# isolated_module_v4.net
KiCad netlist of a schematic drawn in EAGLE
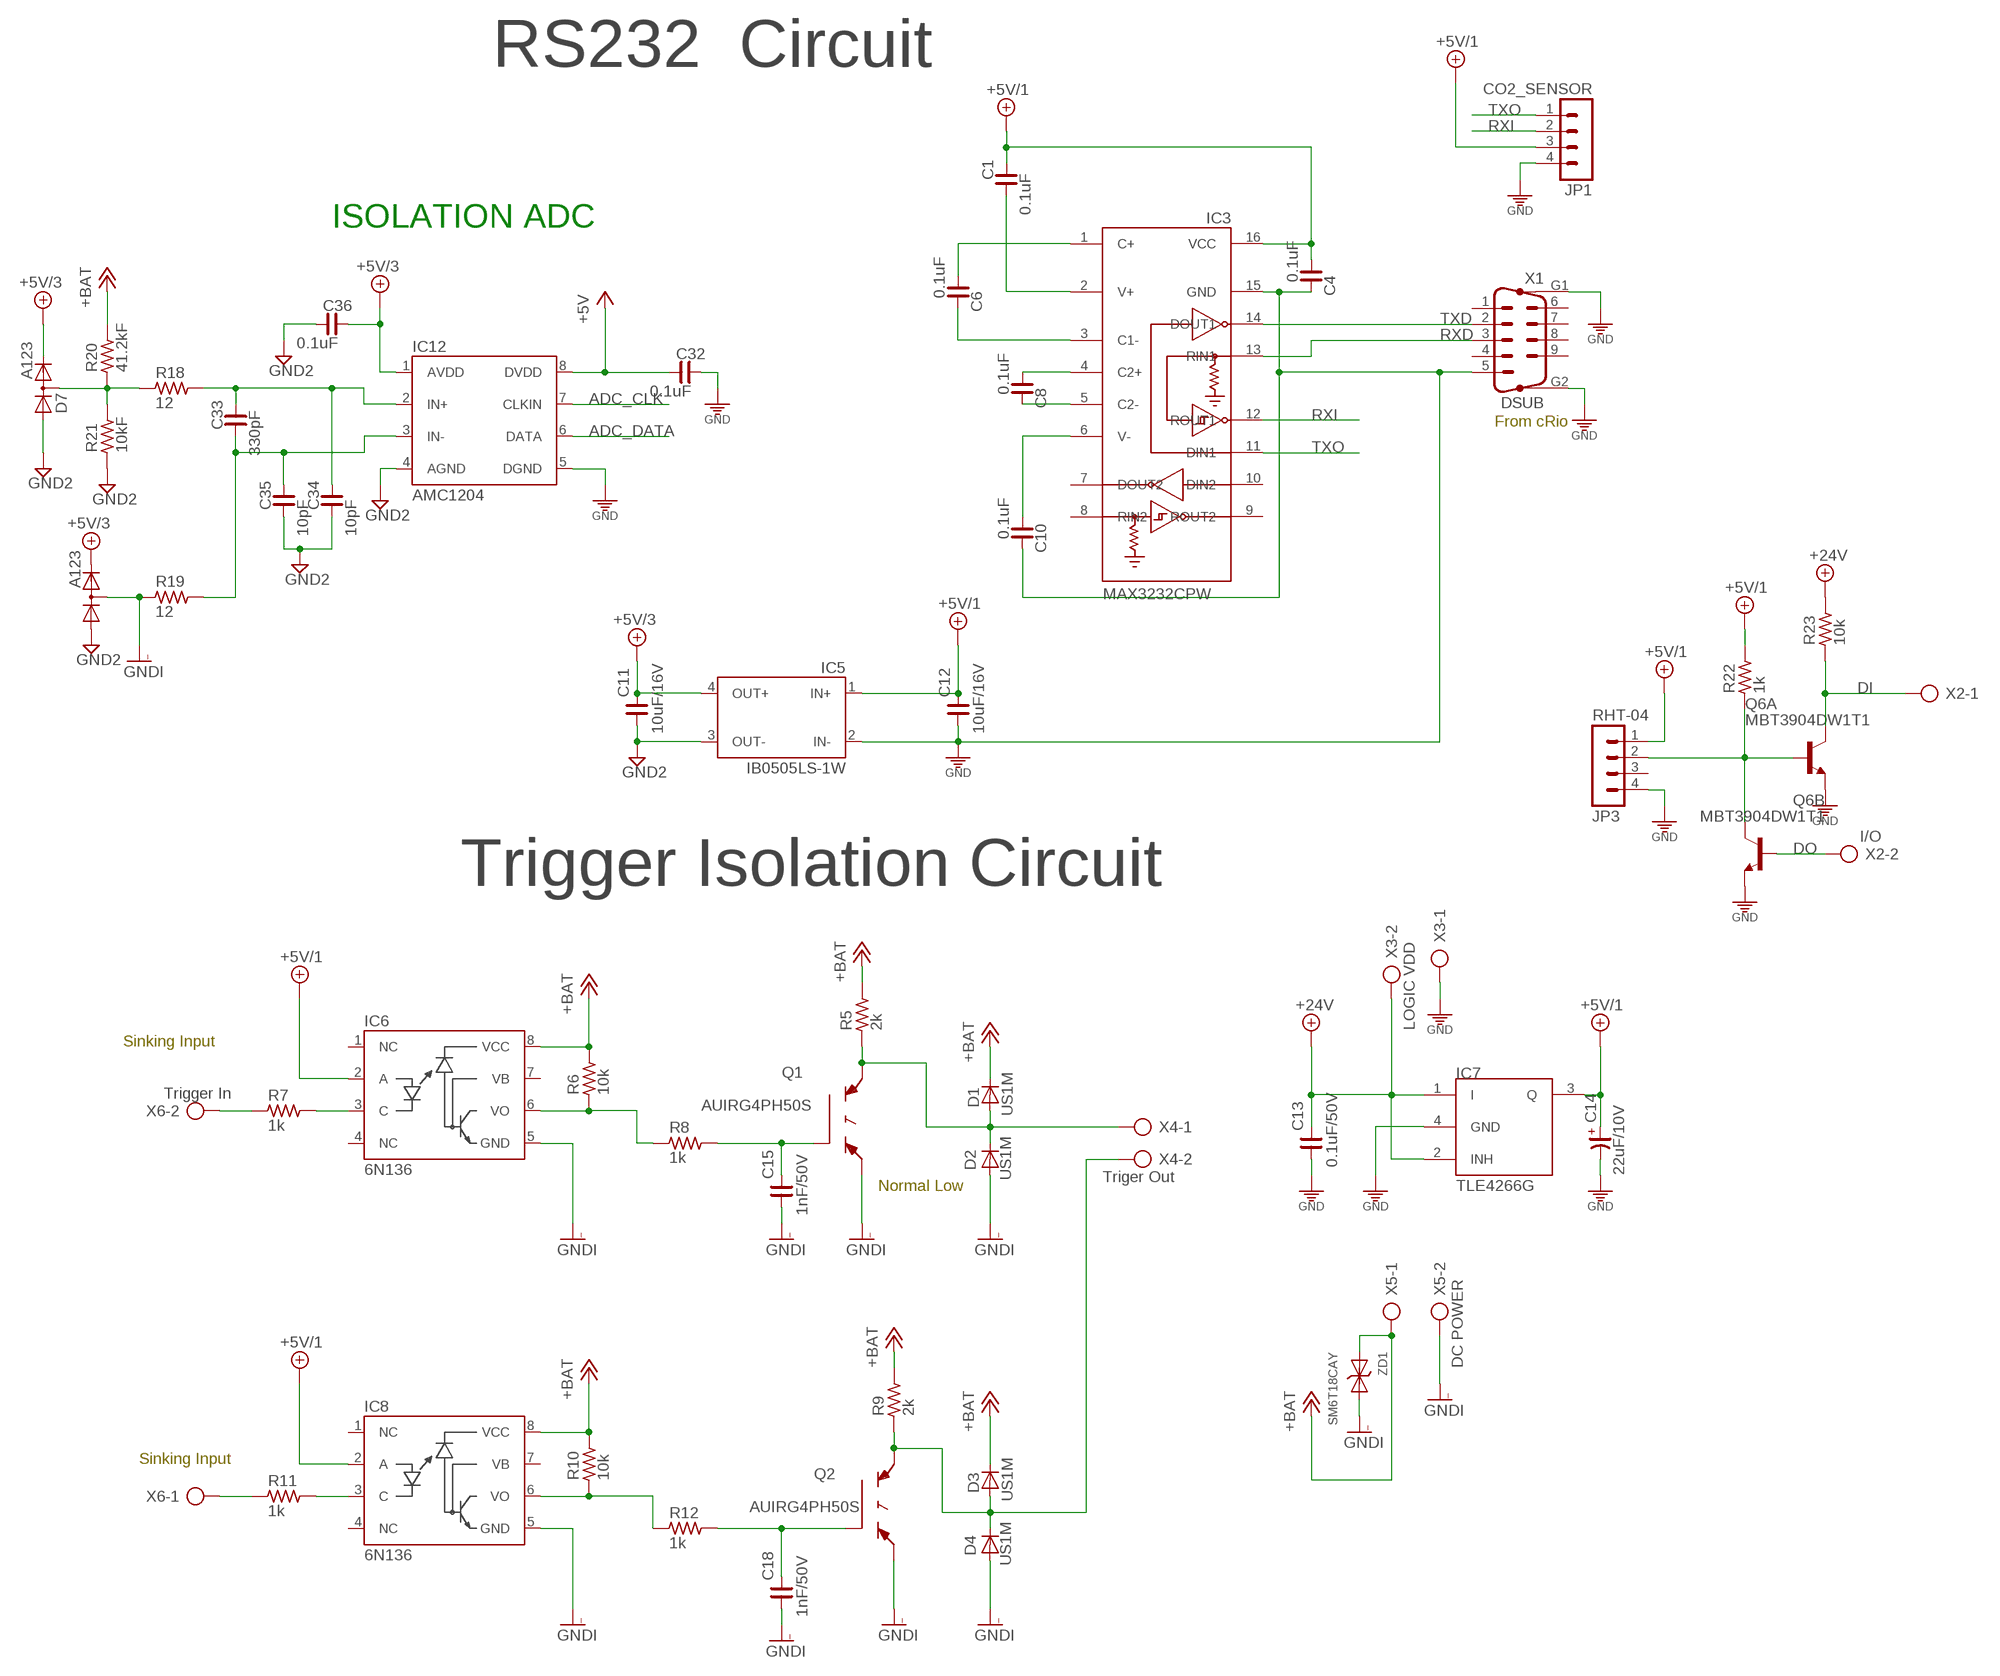
[diagram p0: schematic, sheet 1]

(export (version "E")
  (design (tool "Eeschema 10.0.6"))
  (components
    (comp (ref "C1")
      (value "0.1uF")
      (footprint "eagle-import:C0603")
      (libsource (lib "eagle-import") (part "cona_lib_C_0603"))
    )
    (comp (ref "C4")
      (value "0.1uF")
      (footprint "eagle-import:C0603")
      (libsource (lib "eagle-import") (part "cona_lib_C_0603"))
    )
    (comp (ref "C6")
      (value "0.1uF")
      (footprint "eagle-import:C0603")
      (libsource (lib "eagle-import") (part "cona_lib_C_0603"))
    )
    (comp (ref "C8")
      (value "0.1uF")
      (footprint "eagle-import:C0603")
      (libsource (lib "eagle-import") (part "cona_lib_C_0603"))
    )
    (comp (ref "C10")
      (value "0.1uF")
      (footprint "eagle-import:C0603")
      (libsource (lib "eagle-import") (part "cona_lib_C_0603"))
    )
    (comp (ref "C11")
      (value "10uF/16V")
      (footprint "eagle-import:C1210")
      (libsource (lib "eagle-import") (part "rc-master-smd_C_1210"))
    )
    (comp (ref "C12")
      (value "10uF/16V")
      (footprint "eagle-import:C1210")
      (libsource (lib "eagle-import") (part "rc-master-smd_C_1210"))
    )
    (comp (ref "C13")
      (value "0.1uF/50V")
      (footprint "eagle-import:C1608-")
      (libsource (lib "eagle-import") (part "C_0603"))
    )
    (comp (ref "C14")
      (value "22uF/10V")
      (footprint "eagle-import:T3258")
      (libsource (lib "eagle-import") (part "TANTAL3528"))
    )
    (comp (ref "C15")
      (value "1nF/50V")
      (footprint "eagle-import:C1608-")
      (libsource (lib "eagle-import") (part "C_0603"))
    )
    (comp (ref "C18")
      (value "1nF/50V")
      (footprint "eagle-import:C1608-")
      (libsource (lib "eagle-import") (part "C_0603"))
    )
    (comp (ref "C32")
      (value "0.1uF")
      (footprint "eagle-import:C0603")
      (libsource (lib "eagle-import") (part "cona_lib_C_0603"))
    )
    (comp (ref "C33")
      (value "330pF")
      (footprint "eagle-import:C0603")
      (libsource (lib "eagle-import") (part "cona_lib_C_0603"))
    )
    (comp (ref "C34")
      (value "10pF")
      (footprint "eagle-import:C0603")
      (libsource (lib "eagle-import") (part "cona_lib_C_0603"))
    )
    (comp (ref "C35")
      (value "10pF")
      (footprint "eagle-import:C0603")
      (libsource (lib "eagle-import") (part "cona_lib_C_0603"))
    )
    (comp (ref "C36")
      (value "0.1uF")
      (footprint "eagle-import:C0603")
      (libsource (lib "eagle-import") (part "cona_lib_C_0603"))
    )
    (comp (ref "D1")
      (value "US1M")
      (footprint "eagle-import:DO-214AC")
      (libsource (lib "eagle-import") (part "DIODE-DO-214AC"))
    )
    (comp (ref "D2")
      (value "US1M")
      (footprint "eagle-import:DO-214AC")
      (libsource (lib "eagle-import") (part "DIODE-DO-214AC"))
    )
    (comp (ref "D3")
      (value "US1M")
      (footprint "eagle-import:DO-214AC")
      (libsource (lib "eagle-import") (part "DIODE-DO-214AC"))
    )
    (comp (ref "D4")
      (value "US1M")
      (footprint "eagle-import:DO-214AC")
      (libsource (lib "eagle-import") (part "DIODE-DO-214AC"))
    )
    (comp (ref "D7")
      (value "A123")
      (footprint "eagle-import:SOT23")
      (libsource (lib "eagle-import") (part "DIODE_2CACA-SOT23"))
    )
    (comp (ref "D8")
      (value "A123")
      (footprint "eagle-import:SOT23")
      (libsource (lib "eagle-import") (part "DIODE_2CACA-SOT23"))
    )
    (comp (ref "IC3")
      (value "MAX3232CPW")
      (footprint "eagle-import:PW_R-PDSO-G16")
      (libsource (lib "eagle-import") (part "MAX3232MAX232CPW"))
    )
    (comp (ref "IC5")
      (value "IB0505LS-1W")
      (footprint "eagle-import:DSP1N5S5")
      (libsource (lib "eagle-import") (part "DSP1N5S5"))
    )
    (comp (ref "IC6")
      (value "6N136")
      (footprint "eagle-import:DIL08")
      (libsource (lib "eagle-import") (part "6N136"))
    )
    (comp (ref "IC7")
      (value "TLE4266G")
      (footprint "eagle-import:SOT223-4")
      (libsource (lib "eagle-import") (part "TLE4266G"))
    )
    (comp (ref "IC8")
      (value "6N136")
      (footprint "eagle-import:DIL08")
      (libsource (lib "eagle-import") (part "6N136"))
    )
    (comp (ref "IC12")
      (value "AMC1204")
      (footprint "eagle-import:SO08")
      (libsource (lib "eagle-import") (part "AMC1204"))
    )
    (comp (ref "JP1")
      (value "CO2_SENSOR")
      (footprint "eagle-import:MA04-1-S")
      (libsource (lib "eagle-import") (part "MA04-1SMALL"))
    )
    (comp (ref "JP3")
      (value "RHT-04")
      (footprint "eagle-import:MA04-MOL_N")
      (libsource (lib "eagle-import") (part "MA04-1MOL-N"))
    )
    (comp (ref "Q1")
      (value "AUIRG4PH50S")
      (footprint "eagle-import:TO247AC")
      (libsource (lib "eagle-import") (part "IGBTAC"))
    )
    (comp (ref "Q2")
      (value "AUIRG4PH50S")
      (footprint "eagle-import:TO247AC")
      (libsource (lib "eagle-import") (part "IGBTAC"))
    )
    (comp (ref "Q6")
      (value "MBT3904DW1T1")
      (footprint "eagle-import:UMT6")
      (fields (field (name "MPN") "UMX1NTN"))
      (libsource (lib "eagle-import") (part "UMX1N"))
    )
    (comp (ref "R5")
      (value "2k")
      (footprint "eagle-import:R0805")
      (libsource (lib "eagle-import") (part "R_0805"))
    )
    (comp (ref "R6")
      (value "10k")
      (footprint "eagle-import:R0603")
      (libsource (lib "eagle-import") (part "R_0603"))
    )
    (comp (ref "R7")
      (value "1k")
      (footprint "eagle-import:R0603")
      (libsource (lib "eagle-import") (part "R_0603"))
    )
    (comp (ref "R8")
      (value "1k")
      (footprint "eagle-import:R0603")
      (libsource (lib "eagle-import") (part "R_0603"))
    )
    (comp (ref "R9")
      (value "2k")
      (footprint "eagle-import:R0805")
      (libsource (lib "eagle-import") (part "R_0805"))
    )
    (comp (ref "R10")
      (value "10k")
      (footprint "eagle-import:R0603")
      (libsource (lib "eagle-import") (part "R_0603"))
    )
    (comp (ref "R11")
      (value "1k")
      (footprint "eagle-import:R0603")
      (libsource (lib "eagle-import") (part "R_0603"))
    )
    (comp (ref "R12")
      (value "1k")
      (footprint "eagle-import:R0603")
      (libsource (lib "eagle-import") (part "R_0603"))
    )
    (comp (ref "R18")
      (value "12")
      (footprint "eagle-import:R0603")
      (libsource (lib "eagle-import") (part "R_0603"))
    )
    (comp (ref "R19")
      (value "12")
      (footprint "eagle-import:R0603")
      (libsource (lib "eagle-import") (part "R_0603"))
    )
    (comp (ref "R20")
      (value "41.2kF")
      (footprint "eagle-import:R0603")
      (libsource (lib "eagle-import") (part "R_0603"))
    )
    (comp (ref "R21")
      (value "10kF")
      (footprint "eagle-import:R0603")
      (libsource (lib "eagle-import") (part "R_0603"))
    )
    (comp (ref "R22")
      (value "1k")
      (footprint "eagle-import:R0603")
      (libsource (lib "eagle-import") (part "R_0603"))
    )
    (comp (ref "R23")
      (value "10k")
      (footprint "eagle-import:R0603")
      (libsource (lib "eagle-import") (part "R_0603"))
    )
    (comp (ref "X1")
      (value "DSUB")
      (footprint "eagle-import:M09HP")
      (fields (field (name "OC_FARNELL") "unknown") (field (name "OC_NEWARK") "unknown"))
      (libsource (lib "eagle-import") (part "M09HP"))
    )
    (comp (ref "X2")
      (value "I/O")
      (footprint "eagle-import:AK300_2")
      (libsource (lib "eagle-import") (part "AK300/2"))
    )
    (comp (ref "X3")
      (value "LOGIC VDD")
      (footprint "eagle-import:AK300_2")
      (libsource (lib "eagle-import") (part "AK300/2"))
    )
    (comp (ref "X4")
      (value "Triger Out")
      (footprint "eagle-import:AK300_2")
      (libsource (lib "eagle-import") (part "AK300/2"))
    )
    (comp (ref "X5")
      (value "DC POWER")
      (footprint "eagle-import:AK300_2")
      (libsource (lib "eagle-import") (part "AK300/2"))
    )
    (comp (ref "X6")
      (value "Trigger In")
      (footprint "eagle-import:AK300_2")
      (libsource (lib "eagle-import") (part "AK300/2"))
    )
    (comp (ref "ZD1")
      (value "SM6T18CAY")
      (footprint "eagle-import:SMB")
      (libsource (lib "eagle-import") (part "ZDSM6T33CAY"))
    )
  )
  (nets
    (net (code "1") (name "+5V") (class "Default")
      (node (ref "C32") (pin "2") (pinfunction "2_2") (pintype "passive"))
      (node (ref "IC12") (pin "8") (pinfunction "DVDD_8") (pintype "power_in"))
    )
    (net (code "2") (name "+5V{slash}1") (class "Default")
      (node (ref "C1") (pin "1") (pinfunction "1_1") (pintype "passive"))
      (node (ref "C12") (pin "2") (pinfunction "2_2") (pintype "passive"))
      (node (ref "C14") (pin "+") (pinfunction "+_+") (pintype "passive"))
      (node (ref "C4") (pin "2") (pinfunction "2_2") (pintype "passive"))
      (node (ref "IC3") (pin "16") (pinfunction "VCC_16") (pintype "power_in"))
      (node (ref "IC5") (pin "1") (pinfunction "IN+_1") (pintype "power_in"))
      (node (ref "IC6") (pin "2") (pinfunction "A_2") (pintype "input"))
      (node (ref "IC7") (pin "3") (pinfunction "Q_3") (pintype "power_in"))
      (node (ref "IC8") (pin "2") (pinfunction "A_2") (pintype "input"))
      (node (ref "JP1") (pin "3") (pinfunction "3_3") (pintype "passive"))
      (node (ref "JP3") (pin "1") (pinfunction "1_1") (pintype "passive"))
      (node (ref "R22") (pin "2") (pinfunction "2_2") (pintype "passive"))
    )
    (net (code "3") (name "+5V{slash}3") (class "Default")
      (node (ref "C11") (pin "2") (pinfunction "2_2") (pintype "passive"))
      (node (ref "C36") (pin "1") (pinfunction "1_1") (pintype "passive"))
      (node (ref "D7") (pin "2") (pinfunction "C_2") (pintype "passive"))
      (node (ref "D8") (pin "2") (pinfunction "C_2") (pintype "passive"))
      (node (ref "IC12") (pin "1") (pinfunction "AVDD_1") (pintype "power_in"))
      (node (ref "IC5") (pin "4") (pinfunction "OUT+_4") (pintype "power_in"))
    )
    (net (code "4") (name "+24V") (class "Default")
      (node (ref "C13") (pin "2") (pinfunction "2_2") (pintype "passive"))
      (node (ref "IC7") (pin "1") (pinfunction "I_1") (pintype "power_in"))
      (node (ref "IC7") (pin "2") (pinfunction "INH_2") (pintype "passive"))
      (node (ref "R23") (pin "2") (pinfunction "2_2") (pintype "passive"))
      (node (ref "X3") (pin "2") (pinfunction "KL_2") (pintype "passive"))
    )
    (net (code "5") (name "+BAT") (class "Default")
      (node (ref "D1") (pin "C") (pinfunction "C_C") (pintype "passive"))
      (node (ref "D3") (pin "C") (pinfunction "C_C") (pintype "passive"))
      (node (ref "IC6") (pin "8") (pinfunction "VCC_8") (pintype "power_in"))
      (node (ref "IC8") (pin "8") (pinfunction "VCC_8") (pintype "power_in"))
      (node (ref "R10") (pin "2") (pinfunction "2_2") (pintype "passive"))
      (node (ref "R20") (pin "2") (pinfunction "2_2") (pintype "passive"))
      (node (ref "R5") (pin "2") (pinfunction "2_2") (pintype "passive"))
      (node (ref "R6") (pin "2") (pinfunction "2_2") (pintype "passive"))
      (node (ref "R9") (pin "2") (pinfunction "2_2") (pintype "passive"))
      (node (ref "X5") (pin "1") (pinfunction "KL_1") (pintype "passive"))
      (node (ref "ZD1") (pin "A") (pinfunction "A_A") (pintype "passive"))
    )
    (net (code "6") (name "/ADC_CLK") (class "Default")
      (node (ref "IC12") (pin "7") (pinfunction "CLKIN_7") (pintype "input"))
    )
    (net (code "7") (name "/ADC_DATA") (class "Default")
      (node (ref "IC12") (pin "6") (pinfunction "DATA_6") (pintype "input"))
    )
    (net (code "8") (name "/DI") (class "Default")
      (node (ref "Q6") (pin "6") (pinfunction "C_6") (pintype "passive"))
      (node (ref "R23") (pin "1") (pinfunction "1_1") (pintype "passive"))
      (node (ref "X2") (pin "1") (pinfunction "KL_1") (pintype "passive"))
    )
    (net (code "9") (name "/DO") (class "Default")
      (node (ref "Q6") (pin "5") (pinfunction "B_5") (pintype "passive"))
      (node (ref "X2") (pin "2") (pinfunction "KL_2") (pintype "passive"))
    )
    (net (code "10") (name "/RXD") (class "Default")
      (node (ref "IC3") (pin "13") (pinfunction "RIN1_13") (pintype "input"))
      (node (ref "X1") (pin "3") (pinfunction "3_3") (pintype "passive"))
    )
    (net (code "11") (name "/RXI") (class "Default")
      (node (ref "IC3") (pin "12") (pinfunction "ROUT1_12") (pintype "input"))
      (node (ref "JP1") (pin "2") (pinfunction "2_2") (pintype "passive"))
    )
    (net (code "12") (name "/TXD") (class "Default")
      (node (ref "IC3") (pin "14") (pinfunction "DOUT1_14") (pintype "output"))
      (node (ref "X1") (pin "2") (pinfunction "2_2") (pintype "passive"))
    )
    (net (code "13") (name "/TXO") (class "Default")
      (node (ref "IC3") (pin "11") (pinfunction "DIN1_11") (pintype "input"))
      (node (ref "JP1") (pin "1") (pinfunction "1_1") (pintype "passive"))
    )
    (net (code "14") (name "GND") (class "Default")
      (node (ref "C10") (pin "1") (pinfunction "1_1") (pintype "passive"))
      (node (ref "C12") (pin "1") (pinfunction "1_1") (pintype "passive"))
      (node (ref "C13") (pin "1") (pinfunction "1_1") (pintype "passive"))
      (node (ref "C14") (pin "-") (pinfunction "-_-") (pintype "passive"))
      (node (ref "C32") (pin "1") (pinfunction "1_1") (pintype "passive"))
      (node (ref "C4") (pin "1") (pinfunction "1_1") (pintype "passive"))
      (node (ref "IC12") (pin "5") (pinfunction "DGND_5") (pintype "power_in"))
      (node (ref "IC3") (pin "15") (pinfunction "GND_15") (pintype "power_in"))
      (node (ref "IC5") (pin "2") (pinfunction "IN-_2") (pintype "power_in"))
      (node (ref "IC7") (pin "4") (pinfunction "GND_4") (pintype "power_in"))
      (node (ref "JP1") (pin "4") (pinfunction "4_4") (pintype "passive"))
      (node (ref "JP3") (pin "4") (pinfunction "4_4") (pintype "passive"))
      (node (ref "Q6") (pin "1") (pinfunction "E_1") (pintype "passive"))
      (node (ref "Q6") (pin "4") (pinfunction "E_4") (pintype "passive"))
      (node (ref "X1") (pin "5") (pinfunction "5_5") (pintype "passive"))
      (node (ref "X1") (pin "G1") (pinfunction "G1_G1") (pintype "passive"))
      (node (ref "X1") (pin "G2") (pinfunction "G2_G2") (pintype "passive"))
      (node (ref "X3") (pin "1") (pinfunction "KL_1") (pintype "passive"))
    )
    (net (code "15") (name "GND2") (class "Default")
      (node (ref "C11") (pin "1") (pinfunction "1_1") (pintype "passive"))
      (node (ref "C34") (pin "2") (pinfunction "2_2") (pintype "passive"))
      (node (ref "C35") (pin "2") (pinfunction "2_2") (pintype "passive"))
      (node (ref "C36") (pin "2") (pinfunction "2_2") (pintype "passive"))
      (node (ref "D7") (pin "1") (pinfunction "A_1") (pintype "passive"))
      (node (ref "D8") (pin "1") (pinfunction "A_1") (pintype "passive"))
      (node (ref "IC12") (pin "4") (pinfunction "AGND_4") (pintype "power_in"))
      (node (ref "IC5") (pin "3") (pinfunction "OUT-_3") (pintype "power_in"))
      (node (ref "R21") (pin "1") (pinfunction "1_1") (pintype "passive"))
    )
    (net (code "16") (name "GNDI") (class "Default")
      (node (ref "C15") (pin "1") (pinfunction "1_1") (pintype "passive"))
      (node (ref "C18") (pin "1") (pinfunction "1_1") (pintype "passive"))
      (node (ref "D2") (pin "A") (pinfunction "A_A") (pintype "passive"))
      (node (ref "D4") (pin "A") (pinfunction "A_A") (pintype "passive"))
      (node (ref "D8") (pin "3") (pinfunction "AC_3") (pintype "passive"))
      (node (ref "IC6") (pin "5") (pinfunction "GND_5") (pintype "power_in"))
      (node (ref "IC8") (pin "5") (pinfunction "GND_5") (pintype "power_in"))
      (node (ref "Q1") (pin "E") (pinfunction "E_E") (pintype "passive"))
      (node (ref "Q2") (pin "E") (pinfunction "E_E") (pintype "passive"))
      (node (ref "R19") (pin "1") (pinfunction "1_1") (pintype "passive"))
      (node (ref "X5") (pin "2") (pinfunction "KL_2") (pintype "passive"))
      (node (ref "ZD1") (pin "C") (pinfunction "K_C") (pintype "passive"))
    )
    (net (code "17") (name "Net-(C15-Pad2)") (class "Default")
      (node (ref "C15") (pin "2") (pinfunction "2_2") (pintype "passive"))
      (node (ref "Q1") (pin "G") (pinfunction "G_G") (pintype "passive"))
      (node (ref "R8") (pin "2") (pinfunction "2_2") (pintype "passive"))
    )
    (net (code "18") (name "Net-(C18-Pad2)") (class "Default")
      (node (ref "C18") (pin "2") (pinfunction "2_2") (pintype "passive"))
      (node (ref "Q2") (pin "G") (pinfunction "G_G") (pintype "passive"))
      (node (ref "R12") (pin "2") (pinfunction "2_2") (pintype "passive"))
    )
    (net (code "19") (name "Net-(D7-AC)") (class "Default")
      (node (ref "D7") (pin "3") (pinfunction "AC_3") (pintype "passive"))
      (node (ref "R18") (pin "1") (pinfunction "1_1") (pintype "passive"))
      (node (ref "R20") (pin "1") (pinfunction "1_1") (pintype "passive"))
      (node (ref "R21") (pin "2") (pinfunction "2_2") (pintype "passive"))
    )
    (net (code "20") (name "Net-(IC3-C+)") (class "Default")
      (node (ref "C6") (pin "2") (pinfunction "2_2") (pintype "passive"))
      (node (ref "IC3") (pin "1") (pinfunction "C+_1") (pintype "passive"))
    )
    (net (code "21") (name "Net-(IC3-C1-)") (class "Default")
      (node (ref "C6") (pin "1") (pinfunction "1_1") (pintype "passive"))
      (node (ref "IC3") (pin "3") (pinfunction "C1-_3") (pintype "power_in"))
    )
    (net (code "22") (name "Net-(IC3-C2+)") (class "Default")
      (node (ref "C8") (pin "2") (pinfunction "2_2") (pintype "passive"))
      (node (ref "IC3") (pin "4") (pinfunction "C2+_4") (pintype "passive"))
    )
    (net (code "23") (name "Net-(IC3-C2-)") (class "Default")
      (node (ref "C8") (pin "1") (pinfunction "1_1") (pintype "passive"))
      (node (ref "IC3") (pin "5") (pinfunction "C2-_5") (pintype "passive"))
    )
    (net (code "24") (name "Net-(IC3-V+)") (class "Default")
      (node (ref "C1") (pin "2") (pinfunction "2_2") (pintype "passive"))
      (node (ref "IC3") (pin "2") (pinfunction "V+_2") (pintype "passive"))
    )
    (net (code "25") (name "Net-(IC3-V-)") (class "Default")
      (node (ref "C10") (pin "2") (pinfunction "2_2") (pintype "passive"))
      (node (ref "IC3") (pin "6") (pinfunction "V-_6") (pintype "passive"))
    )
    (net (code "26") (name "Net-(IC6-C)") (class "Default")
      (node (ref "IC6") (pin "3") (pinfunction "C_3") (pintype "input"))
      (node (ref "R7") (pin "2") (pinfunction "2_2") (pintype "passive"))
    )
    (net (code "27") (name "Net-(IC6-VO)") (class "Default")
      (node (ref "IC6") (pin "6") (pinfunction "VO_6") (pintype "output"))
      (node (ref "R6") (pin "1") (pinfunction "1_1") (pintype "passive"))
      (node (ref "R8") (pin "1") (pinfunction "1_1") (pintype "passive"))
    )
    (net (code "28") (name "Net-(IC8-C)") (class "Default")
      (node (ref "IC8") (pin "3") (pinfunction "C_3") (pintype "input"))
      (node (ref "R11") (pin "2") (pinfunction "2_2") (pintype "passive"))
    )
    (net (code "29") (name "Net-(IC8-VO)") (class "Default")
      (node (ref "IC8") (pin "6") (pinfunction "VO_6") (pintype "output"))
      (node (ref "R10") (pin "1") (pinfunction "1_1") (pintype "passive"))
      (node (ref "R12") (pin "1") (pinfunction "1_1") (pintype "passive"))
    )
    (net (code "30") (name "Net-(IC12-IN+)") (class "Default")
      (node (ref "C33") (pin "1") (pinfunction "1_1") (pintype "passive"))
      (node (ref "C34") (pin "1") (pinfunction "1_1") (pintype "passive"))
      (node (ref "IC12") (pin "2") (pinfunction "IN+_2") (pintype "input"))
      (node (ref "R18") (pin "2") (pinfunction "2_2") (pintype "passive"))
    )
    (net (code "31") (name "Net-(IC12-IN-)") (class "Default")
      (node (ref "C33") (pin "2") (pinfunction "2_2") (pintype "passive"))
      (node (ref "C35") (pin "1") (pinfunction "1_1") (pintype "passive"))
      (node (ref "IC12") (pin "3") (pinfunction "IN-_3") (pintype "input"))
      (node (ref "R19") (pin "2") (pinfunction "2_2") (pintype "passive"))
    )
    (net (code "32") (name "Net-(Q6A-B)") (class "Default")
      (node (ref "JP3") (pin "2") (pinfunction "2_2") (pintype "passive"))
      (node (ref "Q6") (pin "2") (pinfunction "B_2") (pintype "passive"))
      (node (ref "Q6") (pin "3") (pinfunction "C_3") (pintype "passive"))
      (node (ref "R22") (pin "1") (pinfunction "1_1") (pintype "passive"))
    )
    (net (code "33") (name "Net-(X4A-KL)") (class "Default")
      (node (ref "D1") (pin "A") (pinfunction "A_A") (pintype "passive"))
      (node (ref "D2") (pin "C") (pinfunction "C_C") (pintype "passive"))
      (node (ref "Q1") (pin "C") (pinfunction "C_C") (pintype "passive"))
      (node (ref "R5") (pin "1") (pinfunction "1_1") (pintype "passive"))
      (node (ref "X4") (pin "1") (pinfunction "KL_1") (pintype "passive"))
    )
    (net (code "34") (name "Net-(X4B-KL)") (class "Default")
      (node (ref "D3") (pin "A") (pinfunction "A_A") (pintype "passive"))
      (node (ref "D4") (pin "C") (pinfunction "C_C") (pintype "passive"))
      (node (ref "Q2") (pin "C") (pinfunction "C_C") (pintype "passive"))
      (node (ref "R9") (pin "1") (pinfunction "1_1") (pintype "passive"))
      (node (ref "X4") (pin "2") (pinfunction "KL_2") (pintype "passive"))
    )
    (net (code "35") (name "Net-(X6A-KL)") (class "Default")
      (node (ref "R11") (pin "1") (pinfunction "1_1") (pintype "passive"))
      (node (ref "X6") (pin "1") (pinfunction "KL_1") (pintype "passive"))
    )
    (net (code "36") (name "Net-(X6B-KL)") (class "Default")
      (node (ref "R7") (pin "1") (pinfunction "1_1") (pintype "passive"))
      (node (ref "X6") (pin "2") (pinfunction "KL_2") (pintype "passive"))
    )
    (net (code "37") (name "unconnected-(IC3-DIN2-Pad10)") (class "Default")
      (node (ref "IC3") (pin "10") (pinfunction "DIN2_10") (pintype "input"))
    )
    (net (code "38") (name "unconnected-(IC3-DOUT2-Pad7)") (class "Default")
      (node (ref "IC3") (pin "7") (pinfunction "DOUT2_7") (pintype "output"))
    )
    (net (code "39") (name "unconnected-(IC3-RIN2-Pad8)") (class "Default")
      (node (ref "IC3") (pin "8") (pinfunction "RIN2_8") (pintype "input"))
    )
    (net (code "40") (name "unconnected-(IC3-ROUT2-Pad9)") (class "Default")
      (node (ref "IC3") (pin "9") (pinfunction "ROUT2_9") (pintype "output"))
    )
    (net (code "41") (name "unconnected-(IC6-NC-Pad1)") (class "Default")
      (node (ref "IC6") (pin "1") (pinfunction "NC_1") (pintype "no_connect"))
    )
    (net (code "42") (name "unconnected-(IC6-NC-Pad4)") (class "Default")
      (node (ref "IC6") (pin "4") (pinfunction "NC_4") (pintype "no_connect"))
    )
    (net (code "43") (name "unconnected-(IC6-VB-Pad7)") (class "Default")
      (node (ref "IC6") (pin "7") (pinfunction "VB_7") (pintype "input"))
    )
    (net (code "44") (name "unconnected-(IC8-NC-Pad1)") (class "Default")
      (node (ref "IC8") (pin "1") (pinfunction "NC_1") (pintype "no_connect"))
    )
    (net (code "45") (name "unconnected-(IC8-NC-Pad4)") (class "Default")
      (node (ref "IC8") (pin "4") (pinfunction "NC_4") (pintype "no_connect"))
    )
    (net (code "46") (name "unconnected-(IC8-VB-Pad7)") (class "Default")
      (node (ref "IC8") (pin "7") (pinfunction "VB_7") (pintype "input"))
    )
    (net (code "47") (name "unconnected-(JP3-Pad3)") (class "Default")
      (node (ref "JP3") (pin "3") (pinfunction "3_3") (pintype "passive"))
    )
    (net (code "48") (name "unconnected-(X1-Pad1)") (class "Default")
      (node (ref "X1") (pin "1") (pinfunction "1_1") (pintype "passive"))
    )
    (net (code "49") (name "unconnected-(X1-Pad4)") (class "Default")
      (node (ref "X1") (pin "4") (pinfunction "4_4") (pintype "passive"))
    )
    (net (code "50") (name "unconnected-(X1-Pad6)") (class "Default")
      (node (ref "X1") (pin "6") (pinfunction "6_6") (pintype "passive"))
    )
    (net (code "51") (name "unconnected-(X1-Pad7)") (class "Default")
      (node (ref "X1") (pin "7") (pinfunction "7_7") (pintype "passive"))
    )
    (net (code "52") (name "unconnected-(X1-Pad8)") (class "Default")
      (node (ref "X1") (pin "8") (pinfunction "8_8") (pintype "passive"))
    )
    (net (code "53") (name "unconnected-(X1-Pad9)") (class "Default")
      (node (ref "X1") (pin "9") (pinfunction "9_9") (pintype "passive"))
    )
  )
)
